# Sheet1.net
KiCad netlist of a schematic drawn in Altium Designer
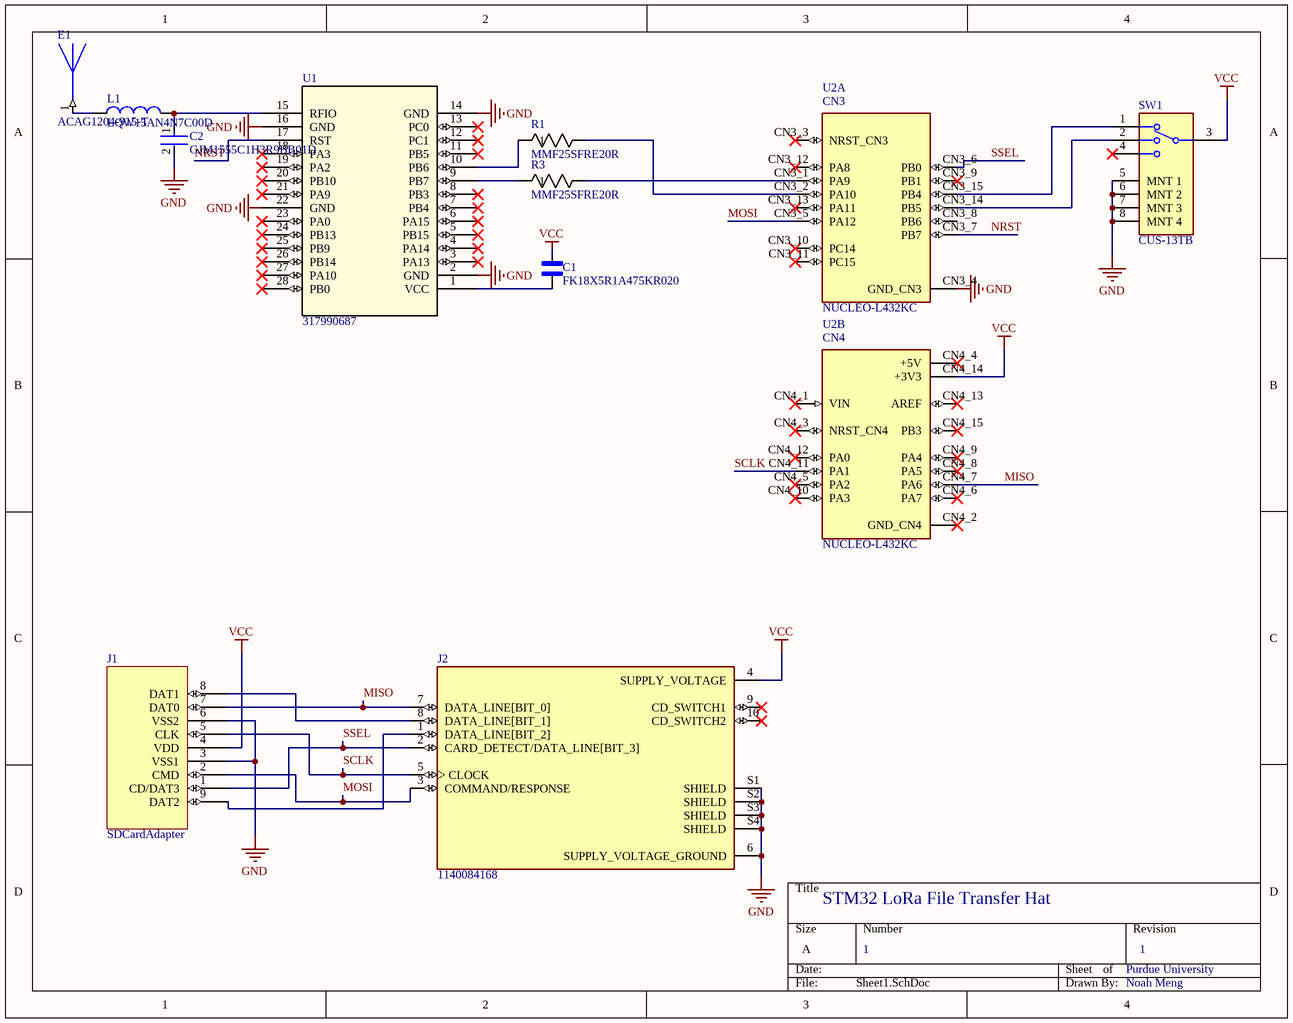
[diagram p0: Sheet1.SchDoc]

(export (version "E")
  (design (tool "Eeschema 10.0.6"))
  (components
    (comp (ref "C1")
      (value "FK18X5R1A475KR020")
      (footprint "CAPRB250W50L400T250H550")
      (fields (field (name "MF") "{'manufacturer': u'TDK Corporation'}"))
      (libsource (lib "Schlib1") (part "FK18X5R1A475KR020"))
    )
    (comp (ref "C2")
      (value "GJM1555C1H3R9BB01D")
      (footprint "FP-GJM155-0_05-IPC_A")
      (description "Multi-Layer Ceramic Capacitor 3.9pF C0G  ±0.1pF 0402 Paper T/R")
      (libsource (lib "Schlib1") (part "CMP-2008-03852-2"))
    )
    (comp (ref "E1")
      (value "ACAG1204-915-T")
      (footprint "XDCR_ACAG1204-915-T")
      (description "915MHz ISM, LoRa, Sigfox Chip RF Antenna 910MHz ~ 925MHz 3.42dBi Solder Surface Mount")
      (fields (field (name "MF") "Abracon LLC"))
      (libsource (lib "Schlib1") (part "ACAG1204-915-T"))
    )
    (comp (ref "J1")
      (value "SDCardAdapter")
      (footprint "PcbLib1:SD Card Adapter")
      (description "SD card adapter")
      (libsource (lib "Schlib1") (part "SDCardAdapter"))
    )
    (comp (ref "J2")
      (value "1140084168")
      (footprint "AMPHENOL_1140084168")
      (description "10 (8 + 2) Position Card Connector Secure Digital - microSDâ„¢ Surface Mount, Right Angle Gold")
      (fields (field (name "MF") "Amphenol ICC"))
      (libsource (lib "Schlib1") (part "1140084168"))
    )
    (comp (ref "L1")
      (value "LQW15AN4N7C00D")
      (footprint "PcbLib1:INDC1006X60N")
      (libsource (lib "Schlib1") (part "LQW15AN4N7C00D"))
    )
    (comp (ref "R1")
      (value "MMF25SFRE20R")
      (footprint "RES_MMF25S_3P5X1P4_YAG")
      (description "No Description Available")
      (libsource (lib "Schlib1") (part "MMF25SFRE20R"))
    )
    (comp (ref "R3")
      (value "MMF25SFRE20R")
      (footprint "RES_MMF25S_3P5X1P4_YAG")
      (description "No Description Available")
      (libsource (lib "Schlib1") (part "MMF25SFRE20R"))
    )
    (comp (ref "SW1")
      (value "CUS-13TB")
      (footprint "FP-CUS-13TB-MFG")
      (description "SWITCH SLIDE SP3T 300MA 4V")
      (libsource (lib "Schlib1") (part "CMP-71745-000014-2"))
    )
    (comp (ref "U1")
      (value "317990687")
      (footprint "QFN_90687_SEE-M")
      (description "No Description Available")
      (libsource (lib "Schlib1") (part "317990687"))
    )
    (comp (ref "U2")
      (value "NUCLEO-L432KC")
      (footprint "MODULE_NUCLEO-L432KC")
      (fields (field (name "MF") "STMicroelectronics"))
      (libsource (lib "Schlib1") (part "NUCLEO-L432KC"))
    )
  )
  (nets
    (net (code "1") (name "/MISO") (class "Default")
      (node (ref "J1") (pin "7") (pinfunction "DAT0_7") (pintype "bidirectional"))
      (node (ref "J2") (pin "7") (pinfunction "DATA_LINE[BIT_0]_7") (pintype "bidirectional"))
      (node (ref "U2") (pin "CN4_7") (pinfunction "PA6_CN4_7") (pintype "bidirectional"))
    )
    (net (code "2") (name "/MOSI") (class "Default")
      (node (ref "J1") (pin "2") (pinfunction "CMD_2") (pintype "bidirectional"))
      (node (ref "J2") (pin "3") (pinfunction "COMMAND/RESPONSE_3") (pintype "bidirectional"))
      (node (ref "U2") (pin "CN3_5") (pinfunction "PA12_CN3_5") (pintype "bidirectional"))
    )
    (net (code "3") (name "/NRST") (class "Default")
      (node (ref "U1") (pin "17") (pinfunction "RST_17") (pintype "passive"))
      (node (ref "U2") (pin "CN3_7") (pinfunction "PB7_CN3_7") (pintype "bidirectional"))
    )
    (net (code "4") (name "/SCLK") (class "Default")
      (node (ref "J1") (pin "5") (pinfunction "CLK_5") (pintype "bidirectional"))
      (node (ref "J2") (pin "5") (pinfunction "CLOCK_5") (pintype "bidirectional"))
      (node (ref "U2") (pin "CN4_11") (pinfunction "PA1_CN4_11") (pintype "bidirectional"))
    )
    (net (code "5") (name "/SSEL") (class "Default")
      (node (ref "J1") (pin "1") (pinfunction "CD/DAT3_1") (pintype "bidirectional"))
      (node (ref "J2") (pin "2") (pinfunction "CARD_DETECT/DATA_LINE[BIT_3]_2") (pintype "bidirectional"))
      (node (ref "U2") (pin "CN3_6") (pinfunction "PB0_CN3_6") (pintype "bidirectional"))
    )
    (net (code "6") (name "GND") (class "Default")
      (node (ref "C2") (pin "2") (pinfunction "2_2") (pintype "passive"))
      (node (ref "J1") (pin "3") (pinfunction "VSS1_3") (pintype "power_in"))
      (node (ref "J1") (pin "6") (pinfunction "VSS2_6") (pintype "power_in"))
      (node (ref "J2") (pin "6") (pinfunction "SUPPLY_VOLTAGE_GROUND_6") (pintype "power_in"))
      (node (ref "J2") (pin "S1") (pinfunction "SHIELD_S1") (pintype "passive"))
      (node (ref "J2") (pin "S2") (pinfunction "SHIELD_S2") (pintype "passive"))
      (node (ref "J2") (pin "S3") (pinfunction "SHIELD_S3") (pintype "passive"))
      (node (ref "J2") (pin "S4") (pinfunction "SHIELD_S4") (pintype "passive"))
      (node (ref "SW1") (pin "5") (pinfunction "MNT_1_5") (pintype "passive"))
      (node (ref "SW1") (pin "6") (pinfunction "MNT_2_6") (pintype "passive"))
      (node (ref "SW1") (pin "7") (pinfunction "MNT_3_7") (pintype "passive"))
      (node (ref "SW1") (pin "8") (pinfunction "MNT_4_8") (pintype "passive"))
      (node (ref "U1") (pin "14") (pinfunction "GND_14") (pintype "power_in"))
      (node (ref "U1") (pin "16") (pinfunction "GND_16") (pintype "power_in"))
      (node (ref "U1") (pin "2") (pinfunction "GND_2") (pintype "power_in"))
      (node (ref "U1") (pin "22") (pinfunction "GND_22") (pintype "power_in"))
      (node (ref "U2") (pin "CN3_4") (pinfunction "GND_CN3_CN3_4") (pintype "power_in"))
    )
    (net (code "7") (name "Net-(E1-Pad1)") (class "Default")
      (node (ref "E1") (pin "1") (pinfunction "1_1") (pintype "input"))
      (node (ref "L1") (pin "1") (pinfunction "1_1") (pintype "passive"))
    )
    (net (code "8") (name "Net-(J1-DAT1)") (class "Default")
      (node (ref "J1") (pin "8") (pinfunction "DAT1_8") (pintype "bidirectional"))
      (node (ref "J2") (pin "8") (pinfunction "DATA_LINE[BIT_1]_8") (pintype "bidirectional"))
    )
    (net (code "9") (name "Net-(J1-DAT2)") (class "Default")
      (node (ref "J1") (pin "9") (pinfunction "DAT2_9") (pintype "bidirectional"))
      (node (ref "J2") (pin "1") (pinfunction "DATA_LINE[BIT_2]_1") (pintype "bidirectional"))
    )
    (net (code "10") (name "Net-(U1-PB6)") (class "Default")
      (node (ref "R1") (pin "1") (pinfunction "1_1") (pintype "passive"))
      (node (ref "U1") (pin "10") (pinfunction "PB6_10") (pintype "bidirectional"))
    )
    (net (code "11") (name "Net-(U1-PB7)") (class "Default")
      (node (ref "R3") (pin "1") (pinfunction "1_1") (pintype "passive"))
      (node (ref "U1") (pin "9") (pinfunction "PB7_9") (pintype "bidirectional"))
    )
    (net (code "12") (name "Net-(U1-RFIO)") (class "Default")
      (node (ref "C2") (pin "1") (pinfunction "1_1") (pintype "passive"))
      (node (ref "L1") (pin "2") (pinfunction "2_2") (pintype "passive"))
      (node (ref "U1") (pin "15") (pinfunction "RFIO_15") (pintype "passive"))
    )
    (net (code "13") (name "Net-(U1-VCC)") (class "Default")
      (node (ref "C1") (pin "1") (pinfunction "1_1") (pintype "passive"))
      (node (ref "U1") (pin "1") (pinfunction "VCC_1") (pintype "power_in"))
    )
    (net (code "14") (name "Net-(U2A-PA9)") (class "Default")
      (node (ref "R3") (pin "2") (pinfunction "2_2") (pintype "passive"))
      (node (ref "U2") (pin "CN3_1") (pinfunction "PA9_CN3_1") (pintype "bidirectional"))
    )
    (net (code "15") (name "Net-(U2A-PA10)") (class "Default")
      (node (ref "R1") (pin "2") (pinfunction "2_2") (pintype "passive"))
      (node (ref "U2") (pin "CN3_2") (pinfunction "PA10_CN3_2") (pintype "bidirectional"))
    )
    (net (code "16") (name "Net-(U2A-PB4)") (class "Default")
      (node (ref "SW1") (pin "1") (pinfunction "1_1") (pintype "passive"))
      (node (ref "U2") (pin "CN3_15") (pinfunction "PB4_CN3_15") (pintype "bidirectional"))
    )
    (net (code "17") (name "Net-(U2A-PB5)") (class "Default")
      (node (ref "SW1") (pin "2") (pinfunction "2_2") (pintype "passive"))
      (node (ref "U2") (pin "CN3_14") (pinfunction "PB5_CN3_14") (pintype "bidirectional"))
    )
    (net (code "18") (name "VCC") (class "Default")
      (node (ref "C1") (pin "2") (pinfunction "2_2") (pintype "passive"))
      (node (ref "J1") (pin "4") (pinfunction "VDD_4") (pintype "power_in"))
      (node (ref "J2") (pin "4") (pinfunction "SUPPLY_VOLTAGE_4") (pintype "power_in"))
      (node (ref "SW1") (pin "3") (pinfunction "C_3") (pintype "passive"))
      (node (ref "U2") (pin "CN4_14") (pinfunction "+3V3_CN4_14") (pintype "power_in"))
    )
    (net (code "19") (name "unconnected-(J2-CD_SWITCH1-Pad9)") (class "Default")
      (node (ref "J2") (pin "9") (pinfunction "CD_SWITCH1_9") (pintype "bidirectional+no_connect"))
    )
    (net (code "20") (name "unconnected-(J2-CD_SWITCH2-Pad10)") (class "Default")
      (node (ref "J2") (pin "10") (pinfunction "CD_SWITCH2_10") (pintype "bidirectional+no_connect"))
    )
    (net (code "21") (name "unconnected-(SW1-Pad4)") (class "Default")
      (node (ref "SW1") (pin "4") (pinfunction "4_4") (pintype "passive+no_connect"))
    )
    (net (code "22") (name "unconnected-(U1-PA0-Pad23)") (class "Default")
      (node (ref "U1") (pin "23") (pinfunction "PA0_23") (pintype "bidirectional+no_connect"))
    )
    (net (code "23") (name "unconnected-(U1-PA2-Pad19)") (class "Default")
      (node (ref "U1") (pin "19") (pinfunction "PA2_19") (pintype "bidirectional+no_connect"))
    )
    (net (code "24") (name "unconnected-(U1-PA3-Pad18)") (class "Default")
      (node (ref "U1") (pin "18") (pinfunction "PA3_18") (pintype "bidirectional+no_connect"))
    )
    (net (code "25") (name "unconnected-(U1-PA9-Pad21)") (class "Default")
      (node (ref "U1") (pin "21") (pinfunction "PA9_21") (pintype "bidirectional+no_connect"))
    )
    (net (code "26") (name "unconnected-(U1-PA10-Pad27)") (class "Default")
      (node (ref "U1") (pin "27") (pinfunction "PA10_27") (pintype "bidirectional+no_connect"))
    )
    (net (code "27") (name "unconnected-(U1-PA13-Pad3)") (class "Default")
      (node (ref "U1") (pin "3") (pinfunction "PA13_3") (pintype "bidirectional+no_connect"))
    )
    (net (code "28") (name "unconnected-(U1-PA14-Pad4)") (class "Default")
      (node (ref "U1") (pin "4") (pinfunction "PA14_4") (pintype "bidirectional+no_connect"))
    )
    (net (code "29") (name "unconnected-(U1-PA15-Pad6)") (class "Default")
      (node (ref "U1") (pin "6") (pinfunction "PA15_6") (pintype "bidirectional+no_connect"))
    )
    (net (code "30") (name "unconnected-(U1-PB0-Pad28)") (class "Default")
      (node (ref "U1") (pin "28") (pinfunction "PB0_28") (pintype "bidirectional+no_connect"))
    )
    (net (code "31") (name "unconnected-(U1-PB3-Pad8)") (class "Default")
      (node (ref "U1") (pin "8") (pinfunction "PB3_8") (pintype "bidirectional+no_connect"))
    )
    (net (code "32") (name "unconnected-(U1-PB4-Pad7)") (class "Default")
      (node (ref "U1") (pin "7") (pinfunction "PB4_7") (pintype "bidirectional+no_connect"))
    )
    (net (code "33") (name "unconnected-(U1-PB5-Pad11)") (class "Default")
      (node (ref "U1") (pin "11") (pinfunction "PB5_11") (pintype "bidirectional+no_connect"))
    )
    (net (code "34") (name "unconnected-(U1-PB9-Pad25)") (class "Default")
      (node (ref "U1") (pin "25") (pinfunction "PB9_25") (pintype "bidirectional+no_connect"))
    )
    (net (code "35") (name "unconnected-(U1-PB10-Pad20)") (class "Default")
      (node (ref "U1") (pin "20") (pinfunction "PB10_20") (pintype "bidirectional+no_connect"))
    )
    (net (code "36") (name "unconnected-(U1-PB13-Pad24)") (class "Default")
      (node (ref "U1") (pin "24") (pinfunction "PB13_24") (pintype "bidirectional+no_connect"))
    )
    (net (code "37") (name "unconnected-(U1-PB14-Pad26)") (class "Default")
      (node (ref "U1") (pin "26") (pinfunction "PB14_26") (pintype "bidirectional+no_connect"))
    )
    (net (code "38") (name "unconnected-(U1-PB15-Pad5)") (class "Default")
      (node (ref "U1") (pin "5") (pinfunction "PB15_5") (pintype "bidirectional+no_connect"))
    )
    (net (code "39") (name "unconnected-(U1-PC0-Pad13)") (class "Default")
      (node (ref "U1") (pin "13") (pinfunction "PC0_13") (pintype "bidirectional+no_connect"))
    )
    (net (code "40") (name "unconnected-(U1-PC1-Pad12)") (class "Default")
      (node (ref "U1") (pin "12") (pinfunction "PC1_12") (pintype "bidirectional+no_connect"))
    )
    (net (code "41") (name "unconnected-(U2A-NRST_CN3-PadCN3_3)") (class "Default")
      (node (ref "U2") (pin "CN3_3") (pinfunction "NRST_CN3_CN3_3") (pintype "bidirectional+no_connect"))
    )
    (net (code "42") (name "unconnected-(U2A-PA8-PadCN3_12)") (class "Default")
      (node (ref "U2") (pin "CN3_12") (pinfunction "PA8_CN3_12") (pintype "bidirectional+no_connect"))
    )
    (net (code "43") (name "unconnected-(U2A-PA11-PadCN3_13)") (class "Default")
      (node (ref "U2") (pin "CN3_13") (pinfunction "PA11_CN3_13") (pintype "bidirectional+no_connect"))
    )
    (net (code "44") (name "unconnected-(U2A-PB1-PadCN3_9)") (class "Default")
      (node (ref "U2") (pin "CN3_9") (pinfunction "PB1_CN3_9") (pintype "bidirectional+no_connect"))
    )
    (net (code "45") (name "unconnected-(U2A-PB6-PadCN3_8)") (class "Default")
      (node (ref "U2") (pin "CN3_8") (pinfunction "PB6_CN3_8") (pintype "bidirectional"))
    )
    (net (code "46") (name "unconnected-(U2A-PC14-PadCN3_10)") (class "Default")
      (node (ref "U2") (pin "CN3_10") (pinfunction "PC14_CN3_10") (pintype "bidirectional+no_connect"))
    )
    (net (code "47") (name "unconnected-(U2A-PC15-PadCN3_11)") (class "Default")
      (node (ref "U2") (pin "CN3_11") (pinfunction "PC15_CN3_11") (pintype "bidirectional+no_connect"))
    )
    (net (code "48") (name "unconnected-(U2B-+5V-PadCN4_4)") (class "Default")
      (node (ref "U2") (pin "CN4_4") (pinfunction "+5V_CN4_4") (pintype "power_in+no_connect"))
    )
    (net (code "49") (name "unconnected-(U2B-AREF-PadCN4_13)") (class "Default")
      (node (ref "U2") (pin "CN4_13") (pinfunction "AREF_CN4_13") (pintype "bidirectional+no_connect"))
    )
    (net (code "50") (name "unconnected-(U2B-GND_CN4-PadCN4_2)") (class "Default")
      (node (ref "U2") (pin "CN4_2") (pinfunction "GND_CN4_CN4_2") (pintype "power_in+no_connect"))
    )
    (net (code "51") (name "unconnected-(U2B-NRST_CN4-PadCN4_3)") (class "Default")
      (node (ref "U2") (pin "CN4_3") (pinfunction "NRST_CN4_CN4_3") (pintype "bidirectional+no_connect"))
    )
    (net (code "52") (name "unconnected-(U2B-PA0-PadCN4_12)") (class "Default")
      (node (ref "U2") (pin "CN4_12") (pinfunction "PA0_CN4_12") (pintype "bidirectional+no_connect"))
    )
    (net (code "53") (name "unconnected-(U2B-PA2-PadCN4_5)") (class "Default")
      (node (ref "U2") (pin "CN4_5") (pinfunction "PA2_CN4_5") (pintype "bidirectional+no_connect"))
    )
    (net (code "54") (name "unconnected-(U2B-PA3-PadCN4_10)") (class "Default")
      (node (ref "U2") (pin "CN4_10") (pinfunction "PA3_CN4_10") (pintype "bidirectional+no_connect"))
    )
    (net (code "55") (name "unconnected-(U2B-PA4-PadCN4_9)") (class "Default")
      (node (ref "U2") (pin "CN4_9") (pinfunction "PA4_CN4_9") (pintype "bidirectional+no_connect"))
    )
    (net (code "56") (name "unconnected-(U2B-PA5-PadCN4_8)") (class "Default")
      (node (ref "U2") (pin "CN4_8") (pinfunction "PA5_CN4_8") (pintype "bidirectional+no_connect"))
    )
    (net (code "57") (name "unconnected-(U2B-PA7-PadCN4_6)") (class "Default")
      (node (ref "U2") (pin "CN4_6") (pinfunction "PA7_CN4_6") (pintype "bidirectional+no_connect"))
    )
    (net (code "58") (name "unconnected-(U2B-PB3-PadCN4_15)") (class "Default")
      (node (ref "U2") (pin "CN4_15") (pinfunction "PB3_CN4_15") (pintype "bidirectional+no_connect"))
    )
    (net (code "59") (name "unconnected-(U2B-VIN-PadCN4_1)") (class "Default")
      (node (ref "U2") (pin "CN4_1") (pinfunction "VIN_CN4_1") (pintype "input+no_connect"))
    )
  )
)
